# FTDI2.net
KiCad netlist of a schematic drawn in Altium Designer
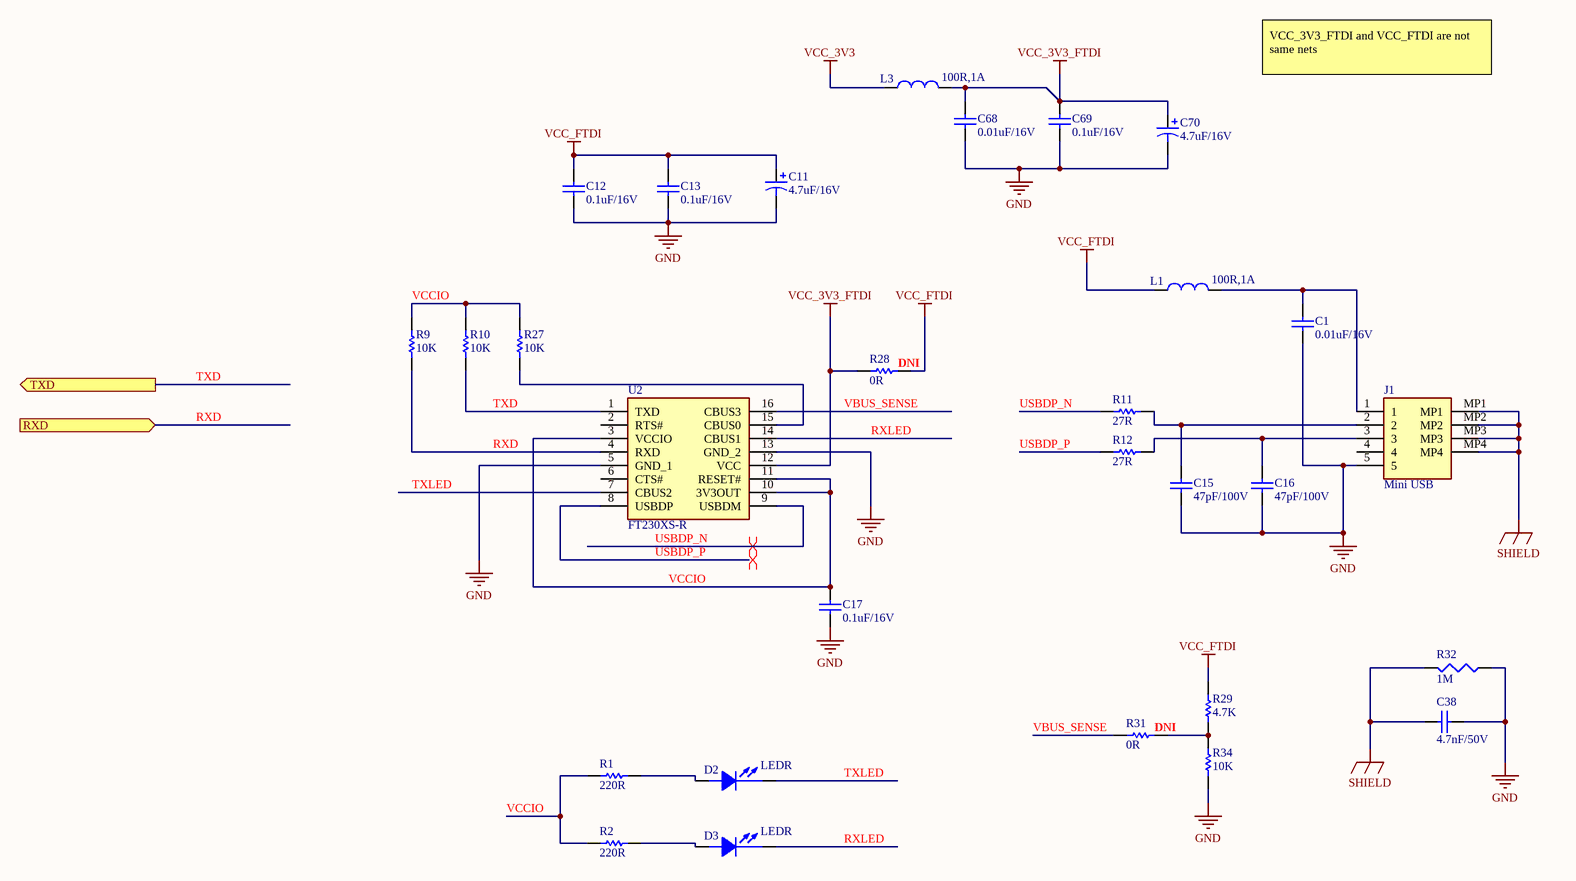
[diagram p0: FTDI2.SchDoc]

(export (version "E")
  (design (tool "Eeschema 10.0.6"))
  (components
    (comp (ref "C1")
      (value "0.01uF/16V")
      (footprint "0603C")
      (description "Multilayer Ceramic Capacitors MLCC - SMD/SMT 16V 0.01uF X7R 0603 10% AEC-Q200")
      (fields (field (name "MFR") "KEMET") (field (name "MFR PART NO") "C0603C103K4RECAUTO"))
      (libsource (lib "Miscellaneous Devices") (part "Cap"))
    )
    (comp (ref "C11")
      (value "4.7uF/16V")
      (description "Tantalum Capacitors - Solid SMD 16V 4.7uF 1206")
      (fields (field (name "MFR") "KEMET") (field (name "MFR PART NO") "T495A475K016ATA2K0"))
      (libsource (lib "Miscellaneous Devices") (part "Cap Pol1"))
    )
    (comp (ref "C12")
      (value "0.1uF/16V")
      (footprint "0603C")
      (description "Multilayer Ceramic Capacitors MLCC - SMD/SMT 0603 16VDC 0.1uF 10% X7R AEC-Q2000")
      (fields (field (name "MFR") "Taiyo Yuden") (field (name "MFR PART NO") "EMK107B7104KAHT"))
      (libsource (lib "Miscellaneous Devices") (part "Cap"))
    )
    (comp (ref "C13")
      (value "0.1uF/16V")
      (footprint "0603C")
      (description "Multilayer Ceramic Capacitors MLCC - SMD/SMT 0603 16VDC 0.1uF 10% X7R AEC-Q2000")
      (fields (field (name "MFR") "Taiyo Yuden") (field (name "MFR PART NO") "EMK107B7104KAHT"))
      (libsource (lib "Miscellaneous Devices") (part "Cap"))
    )
    (comp (ref "C15")
      (value "47pF/100V")
      (footprint "0603C")
      (description "Multilayer Ceramic Capacitors MLCC - SMD/SMT 100V 47pF 0603 X8R 20% AEC-Q200")
      (fields (field (name "MFR") "KEMET") (field (name "MFR PART NO") "C0603C470M1HACAUTO"))
      (libsource (lib "Miscellaneous Devices") (part "Cap"))
    )
    (comp (ref "C16")
      (value "47pF/100V")
      (footprint "0603C")
      (description "Multilayer Ceramic Capacitors MLCC - SMD/SMT 100V 47pF 0603 X8R 20% AEC-Q200")
      (fields (field (name "MFR") "KEMET") (field (name "MFR PART NO") "C0603C470M1HACAUTO"))
      (libsource (lib "Miscellaneous Devices") (part "Cap"))
    )
    (comp (ref "C17")
      (value "0.1uF/16V")
      (footprint "0603C")
      (description "Multilayer Ceramic Capacitors MLCC - SMD/SMT 0603 16VDC 0.1uF 10% X7R AEC-Q2000")
      (fields (field (name "MFR") "Taiyo Yuden") (field (name "MFR PART NO") "EMK107B7104KAHT"))
      (libsource (lib "Miscellaneous Devices") (part "Cap"))
    )
    (comp (ref "C38")
      (value "4.7nF/50V")
      (footprint "0603C")
      (description "Multilayer Ceramic Capacitors MLCC - SMD/SMT 50V 4700pF X7R 0603 10% AEC-Q200")
      (fields
        (field (name "MFR PART NO") "C0603C472K5RACAUTO7411")
        (field (name "STOCKIEST PART NO") "80-C0603C472K5RAUTLR")
      )
      (libsource (lib "Myde10") (part "0805_CAP"))
    )
    (comp (ref "C68")
      (value "0.01uF/16V")
      (footprint "0603C")
      (description "Multilayer Ceramic Capacitors MLCC - SMD/SMT 16V 0.01uF X7R 0603 10% AEC-Q200")
      (fields (field (name "MFR") "KEMET") (field (name "MFR PART NO") "C0603C103K4RECAUTO"))
      (libsource (lib "Miscellaneous Devices") (part "Cap"))
    )
    (comp (ref "C69")
      (value "0.1uF/16V")
      (footprint "0603C")
      (description "Multilayer Ceramic Capacitors MLCC - SMD/SMT 0603 16VDC 0.1uF 10% X7R AEC-Q200")
      (fields (field (name "MFR") "Taiyo Yuden") (field (name "MFR PART NO") "EMK107B7104KAHT"))
      (libsource (lib "Miscellaneous Devices") (part "Cap"))
    )
    (comp (ref "C70")
      (value "4.7uF/16V")
      (description "Tantalum Capacitors - Solid SMD 16V 4.7uF 1206")
      (fields (field (name "MFR") "KEMET") (field (name "MFR PART NO") "T495A475K016ATA2K0"))
      (libsource (lib "Miscellaneous Devices") (part "Cap Pol1"))
    )
    (comp (ref "D2")
      (value "LEDR")
      (footprint "LED_0603")
      (description "Standard LEDs - SMD Red 631nm 14mcd 5mA")
      (fields
        (field (name "STOCKIEST PART NO") "859-LTSTC193KRKT5A")
        (field (name "MFR PART NO") "LTST-C193KRKT-5A")
      )
      (libsource (lib "de20") (part "LED"))
    )
    (comp (ref "D3")
      (value "LEDR")
      (footprint "LED_0603")
      (description "Standard LEDs - SMD Red 631nm 14mcd 5mA")
      (fields
        (field (name "STOCKIEST PART NO") "859-LTSTC193KRKT5A")
        (field (name "MFR PART NO") "LTST-C193KRKT-5A")
      )
      (libsource (lib "de20") (part "LED"))
    )
    (comp (ref "J1")
      (value "Mini USB")
      (description "USB Connectors M-USB 1X1 B/REC R/A SMT")
      (fields (field (name "MFR") "TE Connectivity") (field (name "MFR PART NO") "1734035-2"))
      (libsource (lib "*") (part "10033527-N3112LF"))
    )
    (comp (ref "L1")
      (value "100R,1A")
      (footprint "0603L")
      (description "Ferrite Beads 100ohms 1A 60mOhms 0603 Ferrite Chip")
      (fields (field (name "MFR") "TDK") (field (name "MFR PART NO") "MPZ1608D101BTA00"))
      (libsource (lib "de20") (part "0805_IND"))
    )
    (comp (ref "L3")
      (value "100R,1A")
      (footprint "0603L")
      (description "Ferrite Beads 100ohms 1A 60mOhms 0603 Ferrite Chip")
      (fields (field (name "MFR") "TDK") (field (name "MFR PART NO") "MPZ1608D101BTA00"))
      (libsource (lib "de20") (part "0805_IND"))
    )
    (comp (ref "R1")
      (value "220R")
      (footprint "0603R")
      (description "Thick Film Resistors - SMD 1/10Watt 220ohms 5% Commercial Use")
      (fields (field (name "MFR") "Vishay / Dale") (field (name "MFR PART NO") "CRCW0603220RJNEAC"))
      (libsource (lib "Miscellaneous Devices") (part "Res1"))
    )
    (comp (ref "R2")
      (value "220R")
      (footprint "0603R")
      (description "Thick Film Resistors - SMD 1/10Watt 220ohms 5% Commercial Use")
      (fields (field (name "MFR") "Vishay / Dale") (field (name "MFR PART NO") "CRCW0603220RJNEAC"))
      (libsource (lib "Miscellaneous Devices") (part "Res1"))
    )
    (comp (ref "R9")
      (value "10K")
      (footprint "0603R")
      (description "Thick Film Resistors - SMD 0603 10Kohms 1% Anti-Sulfur AEC-Q200")
      (fields (field (name "MFR") "ROHM Semiconductor") (field (name "MFR PART NO") "SFR03EZPF1002"))
      (libsource (lib "Miscellaneous Devices") (part "Res1"))
    )
    (comp (ref "R10")
      (value "10K")
      (footprint "0603R")
      (description "Thick Film Resistors - SMD 0603 10Kohms 1% Anti-Sulfur AEC-Q200")
      (fields (field (name "MFR") "ROHM Semiconductor") (field (name "MFR PART NO") "SFR03EZPF1002"))
      (libsource (lib "Miscellaneous Devices") (part "Res1"))
    )
    (comp (ref "R11")
      (value "27R")
      (footprint "0603R")
      (description "Thick Film Resistors - SMD 0603 0.25W 1% 27ohm AEC-Q200")
      (fields (field (name "MFR") "Panasonic") (field (name "MFR PART NO") "ERJ-UP3F27R0V"))
      (libsource (lib "Miscellaneous Devices") (part "Res1"))
    )
    (comp (ref "R12")
      (value "27R")
      (footprint "0603R")
      (description "Thick Film Resistors - SMD 0603 0.25W 1% 27ohm AEC-Q200")
      (fields (field (name "MFR") "Panasonic") (field (name "MFR PART NO") "ERJ-UP3F27R0V"))
      (libsource (lib "Miscellaneous Devices") (part "Res1"))
    )
    (comp (ref "R27")
      (value "10K")
      (footprint "0603R")
      (description "Thick Film Resistors - SMD 0603 10Kohms 1% Anti-Sulfur AEC-Q200")
      (fields (field (name "MFR") "ROHM Semiconductor") (field (name "MFR PART NO") "SFR03EZPF1002"))
      (libsource (lib "Miscellaneous Devices") (part "Res1"))
    )
    (comp (ref "R28")
      (value "0R")
      (footprint "AXIAL-0.3")
      (description "Thick Film Resistors - SMD 1/10Watt 0ohms Commercial Use")
      (fields (field (name "MFR") "Vishay / Dale") (field (name "MFR PART NO") "CRCW06030000Z0EAC"))
      (libsource (lib "Miscellaneous Devices") (part "Res1"))
    )
    (comp (ref "R29")
      (value "4.7K")
      (footprint "0603R")
      (description "Thick Film Resistors - SMD 1/10Watt 4.7Kohms 5% Commercial Use")
      (fields (field (name "MFR") "Vishay / Dale") (field (name "MFR PART NO") "CRCW06034K70JNEAC"))
      (libsource (lib "Miscellaneous Devices") (part "Res1"))
    )
    (comp (ref "R31")
      (value "0R")
      (footprint "AXIAL-0.3")
      (description "Thick Film Resistors - SMD 1/10Watt 0ohms Commercial Use")
      (fields (field (name "MFR") "Vishay / Dale") (field (name "MFR PART NO") "CRCW06030000Z0EAC"))
      (libsource (lib "Miscellaneous Devices") (part "Res1"))
    )
    (comp (ref "R32")
      (value "1M")
      (footprint "0603R")
      (description "Thick Film Resistors - SMD 0603 0.25W 1% 1Mohm AEC-Q200")
      (fields
        (field (name "MFR PART NO") "ERJ-UP3F1004V")
        (field (name "STOCKIEST PART NO") "667-ERJ-UP3F1004V")
      )
      (libsource (lib "Myde10") (part "0805_RES"))
    )
    (comp (ref "R34")
      (value "10K")
      (footprint "0603R")
      (description "Thick Film Resistors - SMD 0603 10Kohms 1% Anti-Sulfur AEC-Q200")
      (fields (field (name "MFR") "ROHM Semiconductor") (field (name "MFR PART NO") "SFR03EZPF1002"))
      (libsource (lib "Miscellaneous Devices") (part "Res1"))
    )
    (comp (ref "U2")
      (value "FT230XS-R")
      (description "USB Interface IC USB to Basic Serial UART IC SSOP-16")
      (fields (field (name "MFR") "FTDI") (field (name "STOCKIEST PART NO") "895-FT230XS-R"))
      (libsource (lib "*") (part "FT230"))
    )
  )
  (nets
    (net (code "1") (name "/RXD") (class "Default")
      (node (ref "R9") (pin "2") (pinfunction "2_2") (pintype "passive"))
      (node (ref "U2") (pin "4") (pinfunction "RXD_4") (pintype "passive"))
    )
    (net (code "2") (name "/RXLED") (class "Default")
      (node (ref "D3") (pin "2") (pinfunction "CATHODE_2") (pintype "passive"))
      (node (ref "U2") (pin "14") (pinfunction "CBUS1_14") (pintype "passive"))
    )
    (net (code "3") (name "/TXD") (class "Default")
      (node (ref "R10") (pin "2") (pinfunction "2_2") (pintype "passive"))
      (node (ref "U2") (pin "1") (pinfunction "TXD_1") (pintype "passive"))
    )
    (net (code "4") (name "/TXLED") (class "Default")
      (node (ref "D2") (pin "2") (pinfunction "CATHODE_2") (pintype "passive"))
      (node (ref "U2") (pin "7") (pinfunction "CBUS2_7") (pintype "passive"))
    )
    (net (code "5") (name "/USBDP_N") (class "Default")
      (node (ref "R11") (pin "2") (pinfunction "2_2") (pintype "passive"))
      (node (ref "U2") (pin "9") (pinfunction "USBDM_9") (pintype "passive"))
    )
    (net (code "6") (name "/USBDP_P") (class "Default")
      (node (ref "R12") (pin "2") (pinfunction "2_2") (pintype "passive"))
      (node (ref "U2") (pin "8") (pinfunction "USBDP_8") (pintype "passive"))
    )
    (net (code "7") (name "/VBUS_SENSE") (class "Default")
      (node (ref "R31") (pin "1") (pinfunction "1_1") (pintype "passive"))
      (node (ref "U2") (pin "16") (pinfunction "CBUS3_16") (pintype "passive"))
    )
    (net (code "8") (name "/VCCIO") (class "Default")
      (node (ref "C17") (pin "2") (pinfunction "2_2") (pintype "passive"))
      (node (ref "R1") (pin "2") (pinfunction "2_2") (pintype "passive"))
      (node (ref "R10") (pin "1") (pinfunction "1_1") (pintype "passive"))
      (node (ref "R2") (pin "2") (pinfunction "2_2") (pintype "passive"))
      (node (ref "R27") (pin "1") (pinfunction "1_1") (pintype "passive"))
      (node (ref "R9") (pin "1") (pinfunction "1_1") (pintype "passive"))
      (node (ref "U2") (pin "10") (pinfunction "3V3OUT_10") (pintype "passive"))
      (node (ref "U2") (pin "11") (pinfunction "RESET#_11") (pintype "passive"))
      (node (ref "U2") (pin "3") (pinfunction "VCCIO_3") (pintype "passive"))
    )
    (net (code "9") (name "GND") (class "Default")
      (node (ref "C1") (pin "2") (pinfunction "2_2") (pintype "passive"))
      (node (ref "C11") (pin "2") (pinfunction "2_2") (pintype "passive"))
      (node (ref "C12") (pin "1") (pinfunction "1_1") (pintype "passive"))
      (node (ref "C13") (pin "1") (pinfunction "1_1") (pintype "passive"))
      (node (ref "C15") (pin "1") (pinfunction "1_1") (pintype "passive"))
      (node (ref "C16") (pin "1") (pinfunction "1_1") (pintype "passive"))
      (node (ref "C17") (pin "1") (pinfunction "1_1") (pintype "passive"))
      (node (ref "C38") (pin "1") (pinfunction "1_1") (pintype "passive"))
      (node (ref "C68") (pin "2") (pinfunction "2_2") (pintype "passive"))
      (node (ref "C69") (pin "2") (pinfunction "2_2") (pintype "passive"))
      (node (ref "C70") (pin "2") (pinfunction "2_2") (pintype "passive"))
      (node (ref "J1") (pin "5") (pinfunction "5_5") (pintype "passive"))
      (node (ref "R32") (pin "2") (pinfunction "2_2") (pintype "passive"))
      (node (ref "R34") (pin "2") (pinfunction "2_2") (pintype "passive"))
      (node (ref "U2") (pin "13") (pinfunction "GND_2_13") (pintype "passive"))
      (node (ref "U2") (pin "5") (pinfunction "GND_1_5") (pintype "passive"))
    )
    (net (code "10") (name "Net-(C1-Pad1)") (class "Default")
      (node (ref "C1") (pin "1") (pinfunction "1_1") (pintype "passive"))
      (node (ref "J1") (pin "1") (pinfunction "1_1") (pintype "passive"))
      (node (ref "L1") (pin "2") (pinfunction "2_2") (pintype "passive"))
    )
    (net (code "11") (name "Net-(C15-Pad2)") (class "Default")
      (node (ref "C15") (pin "2") (pinfunction "2_2") (pintype "passive"))
      (node (ref "J1") (pin "2") (pinfunction "2_2") (pintype "passive"))
      (node (ref "R11") (pin "1") (pinfunction "1_1") (pintype "passive"))
    )
    (net (code "12") (name "Net-(C16-Pad2)") (class "Default")
      (node (ref "C16") (pin "2") (pinfunction "2_2") (pintype "passive"))
      (node (ref "J1") (pin "3") (pinfunction "3_3") (pintype "passive"))
      (node (ref "R12") (pin "1") (pinfunction "1_1") (pintype "passive"))
    )
    (net (code "13") (name "Net-(D2-ANODE)") (class "Default")
      (node (ref "D2") (pin "1") (pinfunction "ANODE_1") (pintype "passive"))
      (node (ref "R1") (pin "1") (pinfunction "1_1") (pintype "passive"))
    )
    (net (code "14") (name "Net-(D3-ANODE)") (class "Default")
      (node (ref "D3") (pin "1") (pinfunction "ANODE_1") (pintype "passive"))
      (node (ref "R2") (pin "1") (pinfunction "1_1") (pintype "passive"))
    )
    (net (code "15") (name "Net-(R29-Pad1)") (class "Default")
      (node (ref "R29") (pin "1") (pinfunction "1_1") (pintype "passive"))
      (node (ref "R31") (pin "2") (pinfunction "2_2") (pintype "passive"))
      (node (ref "R34") (pin "1") (pinfunction "1_1") (pintype "passive"))
    )
    (net (code "16") (name "Net-(U2-CBUS0)") (class "Default")
      (node (ref "R27") (pin "2") (pinfunction "2_2") (pintype "passive"))
      (node (ref "U2") (pin "15") (pinfunction "CBUS0_15") (pintype "passive"))
    )
    (net (code "17") (name "SHIELD") (class "Default")
      (node (ref "C38") (pin "2") (pinfunction "2_2") (pintype "passive"))
      (node (ref "J1") (pin "MP1") (pinfunction "MP1_MP1") (pintype "passive"))
      (node (ref "J1") (pin "MP2") (pinfunction "MP2_MP2") (pintype "passive"))
      (node (ref "J1") (pin "MP3") (pinfunction "MP3_MP3") (pintype "passive"))
      (node (ref "J1") (pin "MP4") (pinfunction "MP4_MP4") (pintype "passive"))
      (node (ref "R32") (pin "1") (pinfunction "1_1") (pintype "passive"))
    )
    (net (code "18") (name "VCC_3V3") (class "Default")
      (node (ref "L3") (pin "1") (pinfunction "1_1") (pintype "passive"))
    )
    (net (code "19") (name "VCC_3V3_FTDI") (class "Default")
      (node (ref "C68") (pin "1") (pinfunction "1_1") (pintype "passive"))
      (node (ref "C69") (pin "1") (pinfunction "1_1") (pintype "passive"))
      (node (ref "C70") (pin "1") (pinfunction "1_1") (pintype "passive"))
      (node (ref "L3") (pin "2") (pinfunction "2_2") (pintype "passive"))
      (node (ref "R28") (pin "1") (pinfunction "1_1") (pintype "passive"))
      (node (ref "U2") (pin "12") (pinfunction "VCC_12") (pintype "passive"))
    )
    (net (code "20") (name "VCC_FTDI") (class "Default")
      (node (ref "C11") (pin "1") (pinfunction "1_1") (pintype "passive"))
      (node (ref "C12") (pin "2") (pinfunction "2_2") (pintype "passive"))
      (node (ref "C13") (pin "2") (pinfunction "2_2") (pintype "passive"))
      (node (ref "L1") (pin "1") (pinfunction "1_1") (pintype "passive"))
      (node (ref "R28") (pin "2") (pinfunction "2_2") (pintype "passive"))
      (node (ref "R29") (pin "2") (pinfunction "2_2") (pintype "passive"))
    )
    (net (code "21") (name "unconnected-(J1-Pad4)") (class "Default")
      (node (ref "J1") (pin "4") (pinfunction "4_4") (pintype "passive"))
    )
    (net (code "22") (name "unconnected-(U2-CTS#-Pad6)") (class "Default")
      (node (ref "U2") (pin "6") (pinfunction "CTS#_6") (pintype "passive"))
    )
    (net (code "23") (name "unconnected-(U2-RTS#-Pad2)") (class "Default")
      (node (ref "U2") (pin "2") (pinfunction "RTS#_2") (pintype "passive"))
    )
  )
)
